# CH585M-R1.net
KiCad netlist of a schematic drawn in Altium Designer
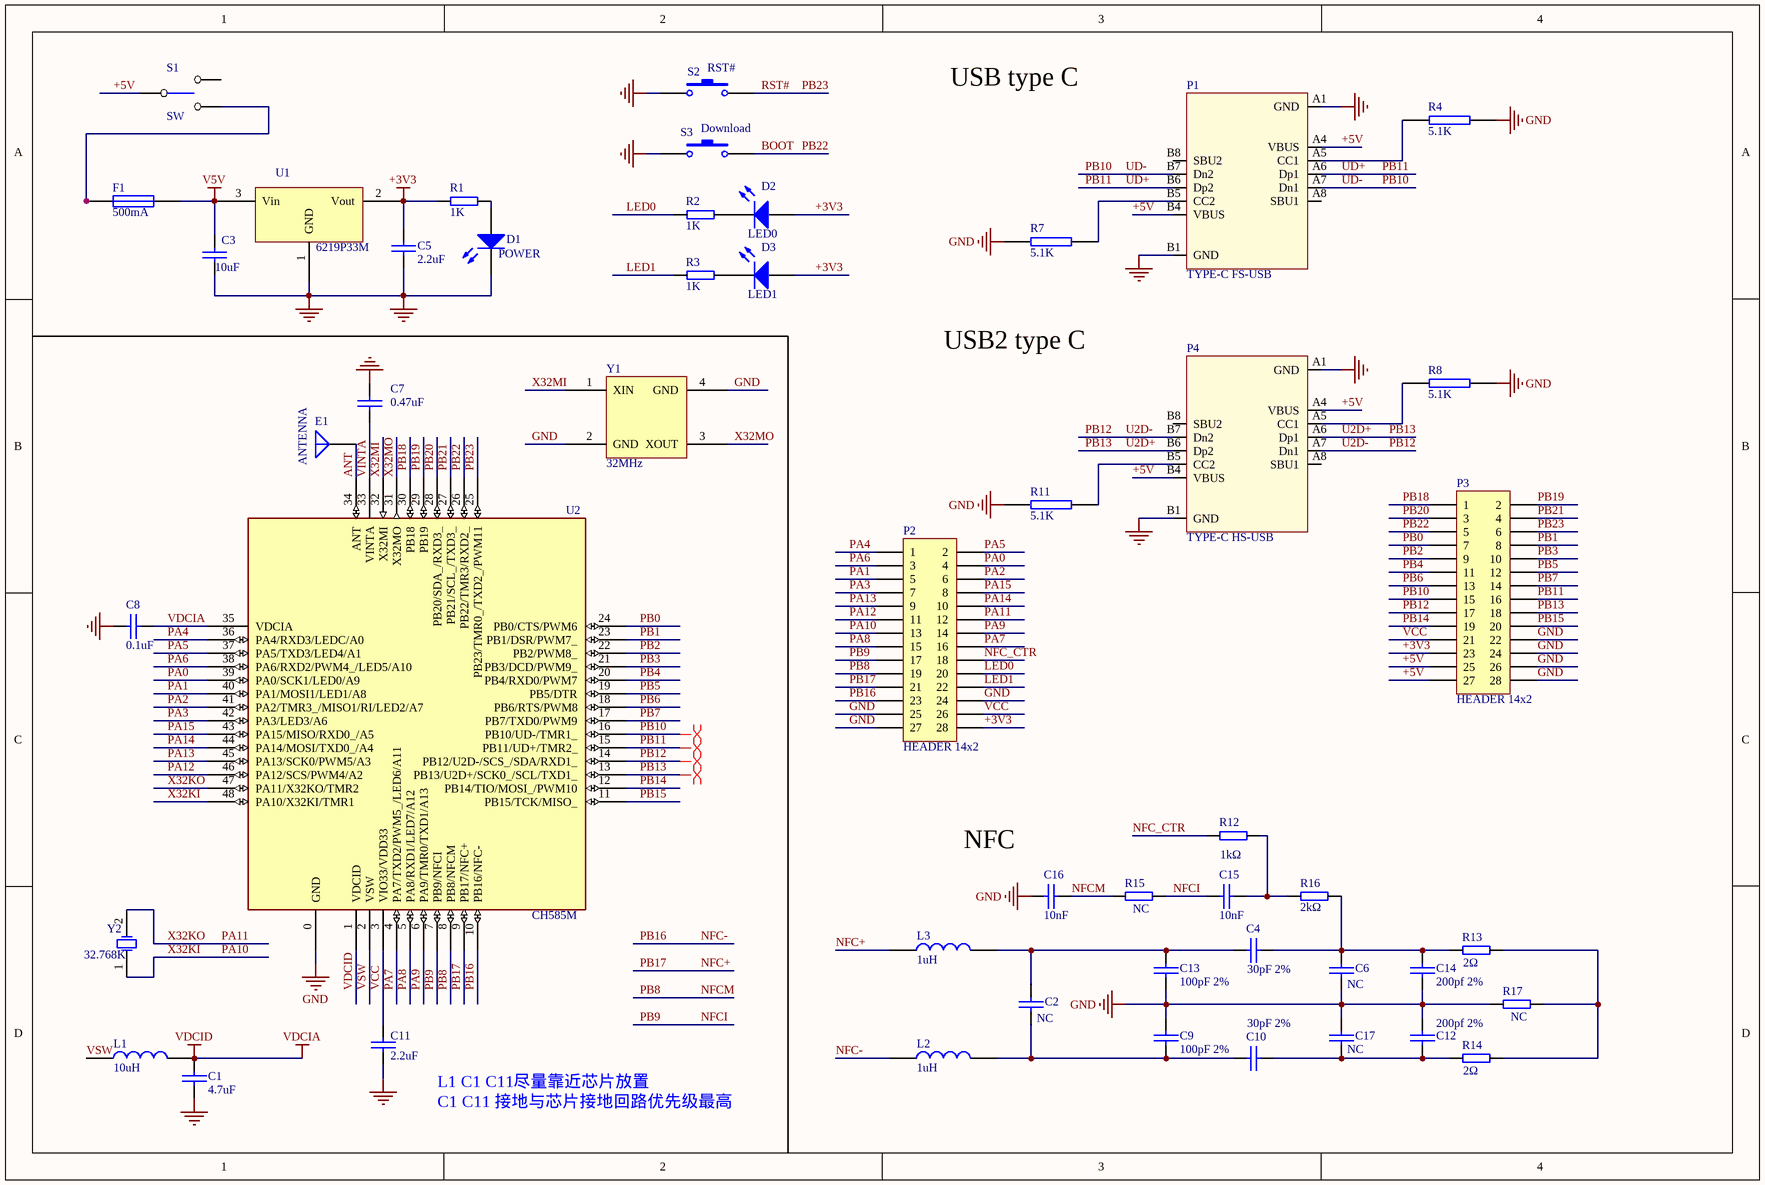
[diagram p0: CH585M-R1.SchDoc]

(export (version "E")
  (design (tool "Eeschema 10.0.6"))
  (components
    (comp (ref "C1")
      (value "4.7uF")
      (footprint "0402_C")
      (description "Capacitor")
      (libsource (lib "*") (part "CAP"))
    )
    (comp (ref "C2")
      (value "NC")
      (footprint "0402_C")
      (description "Capacitor")
      (libsource (lib "wch_sch_others") (part "CAP"))
    )
    (comp (ref "C3")
      (value "10uF")
      (footprint "0603_C")
      (description "Capacitor")
      (libsource (lib "") (part "CAP_1"))
    )
    (comp (ref "C4")
      (value "30pF 2%")
      (footprint "0402_C")
      (description "Capacitor")
      (libsource (lib "wch_sch_others") (part "CAP"))
    )
    (comp (ref "C5")
      (value "2.2uF")
      (footprint "0402_C")
      (description "Capacitor")
      (libsource (lib "") (part "CAP_1"))
    )
    (comp (ref "C6")
      (value "NC")
      (footprint "0402_C")
      (description "Capacitor")
      (libsource (lib "wch_sch_others") (part "CAP"))
    )
    (comp (ref "C7")
      (value "0.47uF")
      (footprint "0402_C")
      (description "Capacitor")
      (libsource (lib "") (part "CAP_1"))
    )
    (comp (ref "C8")
      (value "0.1uF")
      (footprint "0402_C")
      (description "Capacitor")
      (libsource (lib "") (part "CAP_1"))
    )
    (comp (ref "C9")
      (value "100pF 2%")
      (footprint "0402_C")
      (description "Capacitor")
      (libsource (lib "wch_sch_others") (part "CAP"))
    )
    (comp (ref "C10")
      (value "30pF 2%")
      (footprint "0402_C")
      (description "Capacitor")
      (libsource (lib "wch_sch_others") (part "CAP"))
    )
    (comp (ref "C11")
      (value "2.2uF")
      (footprint "0402_C")
      (description "Capacitor")
      (libsource (lib "") (part "CAP_1"))
    )
    (comp (ref "C12")
      (value "200pf 2%")
      (footprint "0402_C")
      (description "Capacitor")
      (libsource (lib "wch_sch_others") (part "CAP"))
    )
    (comp (ref "C13")
      (value "100pF 2%")
      (footprint "0402_C")
      (description "Capacitor")
      (libsource (lib "wch_sch_others") (part "CAP"))
    )
    (comp (ref "C14")
      (value "200pf 2%")
      (footprint "0402_C")
      (description "Capacitor")
      (libsource (lib "wch_sch_others") (part "CAP"))
    )
    (comp (ref "C15")
      (value "10nF")
      (footprint "0402_C")
      (description "Capacitor")
      (libsource (lib "wch_sch_others") (part "CAP"))
    )
    (comp (ref "C16")
      (value "10nF")
      (footprint "0402_C")
      (description "Capacitor")
      (libsource (lib "wch_sch_others") (part "CAP"))
    )
    (comp (ref "C17")
      (value "NC")
      (footprint "0402_C")
      (description "Capacitor")
      (libsource (lib "wch_sch_others") (part "CAP"))
    )
    (comp (ref "D1")
      (value "POWER")
      (footprint "0603+")
      (description "Typical INFRARED GaAs LED")
      (fields (field (name "PUBLISHER") "Altium Limited"))
      (libsource (lib "") (part "LED0_1"))
    )
    (comp (ref "D2")
      (value "LED0")
      (footprint "0603+")
      (description "Typical INFRARED GaAs LED")
      (fields (field (name "PUBLISHER") "Altium Limited"))
      (libsource (lib "Miscellaneous Devices") (part "LED0"))
    )
    (comp (ref "D3")
      (value "LED1")
      (footprint "0603+")
      (description "Typical INFRARED GaAs LED")
      (fields (field (name "PUBLISHER") "Altium Limited"))
      (libsource (lib "Miscellaneous Devices") (part "LED0"))
    )
    (comp (ref "E1")
      (value "ANTENNA")
      (footprint "ANT-F-1-2.4G-1.6mmFR4")
      (description "Generic Antenna")
      (libsource (lib "*") (part "ANTENNA"))
    )
    (comp (ref "F1")
      (value "500mA")
      (footprint "0603")
      (description "Fuse")
      (libsource (lib "*") (part "FUSE1"))
    )
    (comp (ref "L1") (value "10uH") (footprint "SMD_2x2mm") (libsource (lib "*") (part "INDUCTOR")))
    (comp (ref "L2") (value "1uH") (footprint "0603") (libsource (lib "*") (part "INDUCTOR")))
    (comp (ref "L3") (value "1uH") (footprint "0603") (libsource (lib "*") (part "INDUCTOR")))
    (comp (ref "P1")
      (value "TYPE-C FS-USB")
      (footprint "TYPE-C-Receptacle-2.0")
      (description "Type-C USB2.0 母座")
      (libsource (lib "Miscellaneous SCH Lib") (part "TYPE-C-Receptacle-2.0"))
    )
    (comp (ref "P2")
      (value "HEADER 14x2")
      (footprint "MYPCB:IDC28-2.54MM")
      (description "Header, 14-Pin, Dual row")
      (libsource (lib "wch_sch_others") (part "HEADER 14x2"))
    )
    (comp (ref "P3")
      (value "HEADER 14x2")
      (footprint "MYPCB:IDC28-2.54MM")
      (description "Header, 14-Pin, Dual row")
      (libsource (lib "wch_sch_others") (part "HEADER 14x2"))
    )
    (comp (ref "P4")
      (value "TYPE-C HS-USB")
      (footprint "TYPE-C-Receptacle-2.0")
      (description "Type-C USB2.0 母座")
      (libsource (lib "Miscellaneous SCH Lib") (part "TYPE-C-Receptacle-2.0"))
    )
    (comp (ref "R1") (value "1K") (footprint "0402") (libsource (lib "") (part "RES_1")))
    (comp (ref "R2") (value "1K") (footprint "0402") (libsource (lib "") (part "RES_1")))
    (comp (ref "R3") (value "1K") (footprint "0402") (libsource (lib "") (part "RES_1")))
    (comp (ref "R4") (value "5.1K") (footprint "0402") (libsource (lib "*") (part "RES2")))
    (comp (ref "R7") (value "5.1K") (footprint "0402") (libsource (lib "*") (part "RES2")))
    (comp (ref "R8") (value "5.1K") (footprint "0402") (libsource (lib "*") (part "RES2")))
    (comp (ref "R11") (value "5.1K") (footprint "0402") (libsource (lib "*") (part "RES2")))
    (comp (ref "R12") (value "1kΩ") (footprint "0402") (libsource (lib "wch_sch_others") (part "RES")))
    (comp (ref "R13") (value "2Ω") (footprint "0402") (libsource (lib "wch_sch_others") (part "RES")))
    (comp (ref "R14") (value "2Ω") (footprint "0402") (libsource (lib "wch_sch_others") (part "RES")))
    (comp (ref "R15") (value "NC") (footprint "0402") (libsource (lib "wch_sch_others") (part "RES")))
    (comp (ref "R16") (value "2kΩ") (footprint "0402") (libsource (lib "wch_sch_others") (part "RES")))
    (comp (ref "R17") (value "NC") (footprint "0402") (libsource (lib "wch_sch_others") (part "RES")))
    (comp (ref "S1") (value "SW") (footprint "SW1") (libsource (lib "MYSCH") (part "SW")))
    (comp (ref "S2")
      (value "RST#")
      (footprint "SMD_6.1x3.65x2.5mm-KEY")
      (description "Switch")
      (fields (field (name "PUBLISHER") "Altium Limited"))
      (libsource (lib "*") (part "SW-PB"))
    )
    (comp (ref "S3")
      (value "Download")
      (footprint "SMD_6.1x3.65x2.5mm-KEY")
      (description "Switch")
      (fields (field (name "PUBLISHER") "Altium Limited"))
      (libsource (lib "*") (part "SW-PB"))
    )
    (comp (ref "U1")
      (value "6219P33M")
      (footprint "SOT-23")
      (libsource (lib "wch_sch_others") (part "6219P33M"))
    )
    (comp (ref "U2")
      (value "CH585M")
      (footprint "QFN48_5X5")
      (description "RISC-V MCU with BLE/HSUSB/USB/NFC/ADC/PWM/2*SPI/I2C/4*UART/LCD")
      (libsource (lib "CHXXX") (part "CH585M"))
    )
    (comp (ref "Y1") (value "32MHz") (footprint "XT3225") (libsource (lib "wch_sch_others") (part "晶体")))
    (comp (ref "Y2")
      (value "32.768K")
      (footprint "fc-135")
      (description "Crystal Oscillator")
      (fields (field (name "PUBLISHER") "Altium Limited"))
      (libsource (lib "*") (part "XTAL"))
    )
  )
  (nets
    (net (code "1") (name "+3V3") (class "Default")
      (node (ref "C5") (pin "1") (pinfunction "1_1") (pintype "passive"))
      (node (ref "D2") (pin "1") (pinfunction "A_1") (pintype "passive"))
      (node (ref "D3") (pin "1") (pinfunction "A_1") (pintype "passive"))
      (node (ref "P2") (pin "28") (pinfunction "28_28") (pintype "passive"))
      (node (ref "P3") (pin "23") (pinfunction "23_23") (pintype "passive"))
      (node (ref "R1") (pin "2") (pintype "passive"))
      (node (ref "U1") (pin "2") (pinfunction "Vout_2") (pintype "passive"))
    )
    (net (code "2") (name "/+5V") (class "Default")
      (node (ref "P1") (pin "A4") (pinfunction "VBUS_A4") (pintype "passive"))
      (node (ref "P1") (pin "B4") (pinfunction "VBUS_B4") (pintype "passive"))
      (node (ref "P3") (pin "25") (pinfunction "25_25") (pintype "passive"))
      (node (ref "P3") (pin "27") (pinfunction "27_27") (pintype "passive"))
      (node (ref "P4") (pin "A4") (pinfunction "VBUS_A4") (pintype "passive"))
      (node (ref "P4") (pin "B4") (pinfunction "VBUS_B4") (pintype "passive"))
      (node (ref "S1") (pin "1") (pinfunction "1_1") (pintype "passive"))
    )
    (net (code "3") (name "/ANT") (class "Default")
      (node (ref "E1") (pin "1") (pinfunction "A_1") (pintype "passive"))
      (node (ref "U2") (pin "34") (pinfunction "ANT_34") (pintype "bidirectional"))
    )
    (net (code "4") (name "/BOOT") (class "Default")
      (node (ref "P3") (pin "5") (pinfunction "5_5") (pintype "passive"))
      (node (ref "S3") (pin "2") (pinfunction "2_2") (pintype "passive"))
      (node (ref "U2") (pin "26") (pinfunction "PB22/TMR3/RXD2__26") (pintype "bidirectional"))
    )
    (net (code "5") (name "/LED0") (class "Default")
      (node (ref "P2") (pin "20") (pinfunction "20_20") (pintype "passive"))
      (node (ref "R2") (pin "1") (pintype "passive"))
    )
    (net (code "6") (name "/LED1") (class "Default")
      (node (ref "P2") (pin "22") (pinfunction "22_22") (pintype "passive"))
      (node (ref "R3") (pin "1") (pintype "passive"))
    )
    (net (code "7") (name "/NFC+") (class "Default")
      (node (ref "L3") (pin "1") (pinfunction "1_1") (pintype "passive"))
      (node (ref "P2") (pin "21") (pinfunction "21_21") (pintype "passive"))
      (node (ref "U2") (pin "9") (pinfunction "PB17/NFC+_9") (pintype "bidirectional"))
    )
    (net (code "8") (name "/NFC-") (class "Default")
      (node (ref "L2") (pin "1") (pinfunction "1_1") (pintype "passive"))
      (node (ref "P2") (pin "23") (pinfunction "23_23") (pintype "passive"))
      (node (ref "U2") (pin "10") (pinfunction "PB16/NFC-_10") (pintype "bidirectional"))
    )
    (net (code "9") (name "/NFCI") (class "Default")
      (node (ref "C15") (pin "1") (pinfunction "1_1") (pintype "passive"))
      (node (ref "P2") (pin "17") (pinfunction "17_17") (pintype "passive"))
      (node (ref "R15") (pin "1") (pintype "passive"))
      (node (ref "U2") (pin "7") (pinfunction "PB9/NFCI_7") (pintype "bidirectional"))
    )
    (net (code "10") (name "/NFCM") (class "Default")
      (node (ref "C16") (pin "1") (pinfunction "1_1") (pintype "passive"))
      (node (ref "P2") (pin "19") (pinfunction "19_19") (pintype "passive"))
      (node (ref "R15") (pin "2") (pintype "passive"))
      (node (ref "U2") (pin "8") (pinfunction "PB8/NFCM_8") (pintype "bidirectional"))
    )
    (net (code "11") (name "/NFC_CTR") (class "Default")
      (node (ref "P2") (pin "18") (pinfunction "18_18") (pintype "passive"))
      (node (ref "R12") (pin "2") (pintype "passive"))
    )
    (net (code "12") (name "/PA0") (class "Default")
      (node (ref "P2") (pin "4") (pinfunction "4_4") (pintype "passive"))
      (node (ref "U2") (pin "39") (pinfunction "PA0/SCK1/LED0/A9_39") (pintype "bidirectional"))
    )
    (net (code "13") (name "/PA1") (class "Default")
      (node (ref "P2") (pin "5") (pinfunction "5_5") (pintype "passive"))
      (node (ref "U2") (pin "40") (pinfunction "PA1/MOSI1/LED1/A8_40") (pintype "bidirectional"))
    )
    (net (code "14") (name "/PA2") (class "Default")
      (node (ref "P2") (pin "6") (pinfunction "6_6") (pintype "passive"))
      (node (ref "U2") (pin "41") (pinfunction "PA2/TMR3_/MISO1/RI/LED2/A7_41") (pintype "bidirectional"))
    )
    (net (code "15") (name "/PA3") (class "Default")
      (node (ref "P2") (pin "7") (pinfunction "7_7") (pintype "passive"))
      (node (ref "U2") (pin "42") (pinfunction "PA3/LED3/A6_42") (pintype "bidirectional"))
    )
    (net (code "16") (name "/PA4") (class "Default")
      (node (ref "P2") (pin "1") (pinfunction "1_1") (pintype "passive"))
      (node (ref "U2") (pin "36") (pinfunction "PA4/RXD3/LEDC/A0_36") (pintype "bidirectional"))
    )
    (net (code "17") (name "/PA5") (class "Default")
      (node (ref "P2") (pin "2") (pinfunction "2_2") (pintype "passive"))
      (node (ref "U2") (pin "37") (pinfunction "PA5/TXD3/LED4/A1_37") (pintype "bidirectional"))
    )
    (net (code "18") (name "/PA6") (class "Default")
      (node (ref "P2") (pin "3") (pinfunction "3_3") (pintype "passive"))
      (node (ref "U2") (pin "38") (pinfunction "PA6/RXD2/PWM4_/LED5/A10_38") (pintype "bidirectional"))
    )
    (net (code "19") (name "/PA7") (class "Default")
      (node (ref "P2") (pin "16") (pinfunction "16_16") (pintype "passive"))
      (node (ref "U2") (pin "4") (pinfunction "PA7/TXD2/PWM5_/LED6/A11_4") (pintype "bidirectional"))
    )
    (net (code "20") (name "/PA8") (class "Default")
      (node (ref "P2") (pin "15") (pinfunction "15_15") (pintype "passive"))
      (node (ref "U2") (pin "5") (pinfunction "PA8/RXD1/LED7/A12_5") (pintype "bidirectional"))
    )
    (net (code "21") (name "/PA9") (class "Default")
      (node (ref "P2") (pin "14") (pinfunction "14_14") (pintype "passive"))
      (node (ref "U2") (pin "6") (pinfunction "PA9/TMR0/TXD1/A13_6") (pintype "bidirectional"))
    )
    (net (code "22") (name "/PA10") (class "Default")
      (node (ref "P2") (pin "13") (pinfunction "13_13") (pintype "passive"))
      (node (ref "U2") (pin "48") (pinfunction "PA10/X32KI/TMR1_48") (pintype "bidirectional"))
      (node (ref "Y2") (pin "1") (pinfunction "OSC1_1") (pintype "passive"))
    )
    (net (code "23") (name "/PA11") (class "Default")
      (node (ref "P2") (pin "12") (pinfunction "12_12") (pintype "passive"))
      (node (ref "U2") (pin "47") (pinfunction "PA11/X32KO/TMR2_47") (pintype "bidirectional"))
      (node (ref "Y2") (pin "2") (pinfunction "OSC2_2") (pintype "passive"))
    )
    (net (code "24") (name "/PA12") (class "Default")
      (node (ref "P2") (pin "11") (pinfunction "11_11") (pintype "passive"))
      (node (ref "U2") (pin "46") (pinfunction "PA12/SCS/PWM4/A2_46") (pintype "bidirectional"))
    )
    (net (code "25") (name "/PA13") (class "Default")
      (node (ref "P2") (pin "9") (pinfunction "9_9") (pintype "passive"))
      (node (ref "U2") (pin "45") (pinfunction "PA13/SCK0/PWM5/A3_45") (pintype "bidirectional"))
    )
    (net (code "26") (name "/PA14") (class "Default")
      (node (ref "P2") (pin "10") (pinfunction "10_10") (pintype "passive"))
      (node (ref "U2") (pin "44") (pinfunction "PA14/MOSI/TXD0_/A4_44") (pintype "bidirectional"))
    )
    (net (code "27") (name "/PA15") (class "Default")
      (node (ref "P2") (pin "8") (pinfunction "8_8") (pintype "passive"))
      (node (ref "U2") (pin "43") (pinfunction "PA15/MISO/RXD0_/A5_43") (pintype "bidirectional"))
    )
    (net (code "28") (name "/PB0") (class "Default")
      (node (ref "P3") (pin "7") (pinfunction "7_7") (pintype "passive"))
      (node (ref "U2") (pin "24") (pinfunction "PB0/CTS/PWM6_24") (pintype "bidirectional"))
    )
    (net (code "29") (name "/PB1") (class "Default")
      (node (ref "P3") (pin "8") (pinfunction "8_8") (pintype "passive"))
      (node (ref "U2") (pin "23") (pinfunction "PB1/DSR/PWM7__23") (pintype "bidirectional"))
    )
    (net (code "30") (name "/PB2") (class "Default")
      (node (ref "P3") (pin "9") (pinfunction "9_9") (pintype "passive"))
      (node (ref "U2") (pin "22") (pinfunction "PB2/PWM8__22") (pintype "bidirectional"))
    )
    (net (code "31") (name "/PB3") (class "Default")
      (node (ref "P3") (pin "10") (pinfunction "10_10") (pintype "passive"))
      (node (ref "U2") (pin "21") (pinfunction "PB3/DCD/PWM9__21") (pintype "bidirectional"))
    )
    (net (code "32") (name "/PB4") (class "Default")
      (node (ref "P3") (pin "11") (pinfunction "11_11") (pintype "passive"))
      (node (ref "U2") (pin "20") (pinfunction "PB4/RXD0/PWM7_20") (pintype "bidirectional"))
    )
    (net (code "33") (name "/PB5") (class "Default")
      (node (ref "P3") (pin "12") (pinfunction "12_12") (pintype "passive"))
      (node (ref "U2") (pin "19") (pinfunction "PB5/DTR_19") (pintype "bidirectional"))
    )
    (net (code "34") (name "/PB6") (class "Default")
      (node (ref "P3") (pin "13") (pinfunction "13_13") (pintype "passive"))
      (node (ref "U2") (pin "18") (pinfunction "PB6/RTS/PWM8_18") (pintype "bidirectional"))
    )
    (net (code "35") (name "/PB7") (class "Default")
      (node (ref "P3") (pin "14") (pinfunction "14_14") (pintype "passive"))
      (node (ref "U2") (pin "17") (pinfunction "PB7/TXD0/PWM9_17") (pintype "bidirectional"))
    )
    (net (code "36") (name "/PB10") (class "Default")
      (node (ref "P1") (pin "A7") (pinfunction "Dn1_A7") (pintype "passive"))
      (node (ref "P1") (pin "B7") (pinfunction "Dn2_B7") (pintype "passive"))
      (node (ref "P3") (pin "15") (pinfunction "15_15") (pintype "passive"))
      (node (ref "U2") (pin "16") (pinfunction "PB10/UD-/TMR1__16") (pintype "bidirectional"))
    )
    (net (code "37") (name "/PB11") (class "Default")
      (node (ref "P1") (pin "A6") (pinfunction "Dp1_A6") (pintype "passive"))
      (node (ref "P1") (pin "B6") (pinfunction "Dp2_B6") (pintype "passive"))
      (node (ref "P3") (pin "16") (pinfunction "16_16") (pintype "passive"))
      (node (ref "U2") (pin "15") (pinfunction "PB11/UD+/TMR2__15") (pintype "bidirectional"))
    )
    (net (code "38") (name "/PB12") (class "Default")
      (node (ref "P3") (pin "17") (pinfunction "17_17") (pintype "passive"))
      (node (ref "P4") (pin "A7") (pinfunction "Dn1_A7") (pintype "passive"))
      (node (ref "P4") (pin "B7") (pinfunction "Dn2_B7") (pintype "passive"))
      (node (ref "U2") (pin "14") (pinfunction "PB12/U2D-/SCS_/SDA/RXD1__14") (pintype "bidirectional"))
    )
    (net (code "39") (name "/PB13") (class "Default")
      (node (ref "P3") (pin "18") (pinfunction "18_18") (pintype "passive"))
      (node (ref "P4") (pin "A6") (pinfunction "Dp1_A6") (pintype "passive"))
      (node (ref "P4") (pin "B6") (pinfunction "Dp2_B6") (pintype "passive"))
      (node (ref "U2") (pin "13") (pinfunction "PB13/U2D+/SCK0_/SCL/TXD1__13") (pintype "bidirectional"))
    )
    (net (code "40") (name "/PB14") (class "Default")
      (node (ref "P3") (pin "19") (pinfunction "19_19") (pintype "passive"))
      (node (ref "U2") (pin "12") (pinfunction "PB14/TIO/MOSI_/PWM10_12") (pintype "bidirectional"))
    )
    (net (code "41") (name "/PB15") (class "Default")
      (node (ref "P3") (pin "20") (pinfunction "20_20") (pintype "passive"))
      (node (ref "U2") (pin "11") (pinfunction "PB15/TCK/MISO__11") (pintype "bidirectional"))
    )
    (net (code "42") (name "/PB18") (class "Default")
      (node (ref "P3") (pin "1") (pinfunction "1_1") (pintype "passive"))
      (node (ref "U2") (pin "30") (pinfunction "PB18_30") (pintype "bidirectional"))
    )
    (net (code "43") (name "/PB19") (class "Default")
      (node (ref "P3") (pin "2") (pinfunction "2_2") (pintype "passive"))
      (node (ref "U2") (pin "29") (pinfunction "PB19_29") (pintype "bidirectional"))
    )
    (net (code "44") (name "/PB20") (class "Default")
      (node (ref "P3") (pin "3") (pinfunction "3_3") (pintype "passive"))
      (node (ref "U2") (pin "28") (pinfunction "PB20/SDA_/RXD3__28") (pintype "bidirectional"))
    )
    (net (code "45") (name "/PB21") (class "Default")
      (node (ref "P3") (pin "4") (pinfunction "4_4") (pintype "passive"))
      (node (ref "U2") (pin "27") (pinfunction "PB21/SCL_/TXD3__27") (pintype "bidirectional"))
    )
    (net (code "46") (name "/PB23") (class "Default")
      (node (ref "P3") (pin "6") (pinfunction "6_6") (pintype "passive"))
      (node (ref "S2") (pin "2") (pinfunction "2_2") (pintype "passive"))
      (node (ref "U2") (pin "25") (pinfunction "PB23/TMR0_/TXD2_/PWM11_25") (pintype "bidirectional"))
    )
    (net (code "47") (name "/VCC") (class "Default")
      (node (ref "C11") (pin "2") (pinfunction "2_2") (pintype "passive"))
      (node (ref "P2") (pin "26") (pinfunction "26_26") (pintype "passive"))
      (node (ref "P3") (pin "21") (pinfunction "21_21") (pintype "passive"))
      (node (ref "U2") (pin "3") (pinfunction "VIO33/VDD33_3") (pintype "power_in"))
    )
    (net (code "48") (name "/VINTA") (class "Default")
      (node (ref "C7") (pin "1") (pinfunction "1_1") (pintype "passive"))
      (node (ref "U2") (pin "33") (pinfunction "VINTA_33") (pintype "power_in"))
    )
    (net (code "49") (name "/VSW") (class "Default")
      (node (ref "L1") (pin "1") (pinfunction "1_1") (pintype "passive"))
      (node (ref "U2") (pin "2") (pinfunction "VSW_2") (pintype "power_in"))
    )
    (net (code "50") (name "/X32MI") (class "Default")
      (node (ref "U2") (pin "32") (pinfunction "X32MI_32") (pintype "input"))
      (node (ref "Y1") (pin "1") (pinfunction "XIN_1") (pintype "passive"))
    )
    (net (code "51") (name "/X32MO") (class "Default")
      (node (ref "U2") (pin "31") (pinfunction "X32MO_31") (pintype "output"))
      (node (ref "Y1") (pin "3") (pinfunction "XOUT_3") (pintype "passive"))
    )
    (net (code "52") (name "GND") (class "Default")
      (node (ref "C1") (pin "1") (pinfunction "1_1") (pintype "passive"))
      (node (ref "C11") (pin "1") (pinfunction "1_1") (pintype "passive"))
      (node (ref "C12") (pin "2") (pinfunction "2_2") (pintype "passive"))
      (node (ref "C13") (pin "1") (pinfunction "1_1") (pintype "passive"))
      (node (ref "C14") (pin "1") (pinfunction "1_1") (pintype "passive"))
      (node (ref "C16") (pin "2") (pinfunction "2_2") (pintype "passive"))
      (node (ref "C17") (pin "2") (pinfunction "2_2") (pintype "passive"))
      (node (ref "C3") (pin "2") (pinfunction "2_2") (pintype "passive"))
      (node (ref "C5") (pin "2") (pinfunction "2_2") (pintype "passive"))
      (node (ref "C6") (pin "1") (pinfunction "1_1") (pintype "passive"))
      (node (ref "C7") (pin "2") (pinfunction "2_2") (pintype "passive"))
      (node (ref "C8") (pin "2") (pinfunction "2_2") (pintype "passive"))
      (node (ref "C9") (pin "2") (pinfunction "2_2") (pintype "passive"))
      (node (ref "D1") (pin "2") (pinfunction "K_2") (pintype "passive"))
      (node (ref "P1") (pin "A1") (pinfunction "GND_A1") (pintype "passive"))
      (node (ref "P1") (pin "B1") (pinfunction "GND_B1") (pintype "passive"))
      (node (ref "P2") (pin "24") (pinfunction "24_24") (pintype "passive"))
      (node (ref "P2") (pin "25") (pinfunction "25_25") (pintype "passive"))
      (node (ref "P2") (pin "27") (pinfunction "27_27") (pintype "passive"))
      (node (ref "P3") (pin "22") (pinfunction "22_22") (pintype "passive"))
      (node (ref "P3") (pin "24") (pinfunction "24_24") (pintype "passive"))
      (node (ref "P3") (pin "26") (pinfunction "26_26") (pintype "passive"))
      (node (ref "P3") (pin "28") (pinfunction "28_28") (pintype "passive"))
      (node (ref "P4") (pin "A1") (pinfunction "GND_A1") (pintype "passive"))
      (node (ref "P4") (pin "B1") (pinfunction "GND_B1") (pintype "passive"))
      (node (ref "R11") (pin "2") (pinfunction "2_2") (pintype "passive"))
      (node (ref "R17") (pin "2") (pintype "passive"))
      (node (ref "R4") (pin "1") (pinfunction "1_1") (pintype "passive"))
      (node (ref "R7") (pin "2") (pinfunction "2_2") (pintype "passive"))
      (node (ref "R8") (pin "1") (pinfunction "1_1") (pintype "passive"))
      (node (ref "S2") (pin "1") (pinfunction "1_1") (pintype "passive"))
      (node (ref "S3") (pin "1") (pinfunction "1_1") (pintype "passive"))
      (node (ref "U1") (pin "1") (pinfunction "GND_1") (pintype "passive"))
      (node (ref "U2") (pin "0") (pinfunction "GND_0") (pintype "power_in"))
      (node (ref "Y1") (pin "2") (pinfunction "GND_2") (pintype "passive"))
      (node (ref "Y1") (pin "4") (pinfunction "GND_4") (pintype "passive"))
    )
    (net (code "53") (name "Net-(C10-Pad1)") (class "Default")
      (node (ref "C10") (pin "1") (pinfunction "1_1") (pintype "passive"))
      (node (ref "C2") (pin "1") (pinfunction "1_1") (pintype "passive"))
      (node (ref "C9") (pin "1") (pinfunction "1_1") (pintype "passive"))
      (node (ref "L2") (pin "2") (pinfunction "2_2") (pintype "passive"))
    )
    (net (code "54") (name "Net-(C10-Pad2)") (class "Default")
      (node (ref "C10") (pin "2") (pinfunction "2_2") (pintype "passive"))
      (node (ref "C12") (pin "1") (pinfunction "1_1") (pintype "passive"))
      (node (ref "C17") (pin "1") (pinfunction "1_1") (pintype "passive"))
      (node (ref "R14") (pin "1") (pintype "passive"))
    )
    (net (code "55") (name "Net-(C13-Pad2)") (class "Default")
      (node (ref "C13") (pin "2") (pinfunction "2_2") (pintype "passive"))
      (node (ref "C2") (pin "2") (pinfunction "2_2") (pintype "passive"))
      (node (ref "C4") (pin "1") (pinfunction "1_1") (pintype "passive"))
      (node (ref "L3") (pin "2") (pinfunction "2_2") (pintype "passive"))
    )
    (net (code "56") (name "Net-(C14-Pad2)") (class "Default")
      (node (ref "C14") (pin "2") (pinfunction "2_2") (pintype "passive"))
      (node (ref "C4") (pin "2") (pinfunction "2_2") (pintype "passive"))
      (node (ref "C6") (pin "2") (pinfunction "2_2") (pintype "passive"))
      (node (ref "R13") (pin "1") (pintype "passive"))
      (node (ref "R16") (pin "1") (pintype "passive"))
    )
    (net (code "57") (name "Net-(C15-Pad2)") (class "Default")
      (node (ref "C15") (pin "2") (pinfunction "2_2") (pintype "passive"))
      (node (ref "R12") (pin "1") (pintype "passive"))
      (node (ref "R16") (pin "2") (pintype "passive"))
    )
    (net (code "58") (name "Net-(D1-A)") (class "Default")
      (node (ref "D1") (pin "1") (pinfunction "A_1") (pintype "passive"))
      (node (ref "R1") (pin "1") (pintype "passive"))
    )
    (net (code "59") (name "Net-(D2-K)") (class "Default")
      (node (ref "D2") (pin "2") (pinfunction "K_2") (pintype "passive"))
      (node (ref "R2") (pin "2") (pintype "passive"))
    )
    (net (code "60") (name "Net-(D3-K)") (class "Default")
      (node (ref "D3") (pin "2") (pinfunction "K_2") (pintype "passive"))
      (node (ref "R3") (pin "2") (pintype "passive"))
    )
    (net (code "61") (name "Net-(F1-Pad1)") (class "Default")
      (node (ref "F1") (pin "1") (pinfunction "1_1") (pintype "passive"))
      (node (ref "S1") (pin "2") (pinfunction "2_2") (pintype "passive"))
    )
    (net (code "62") (name "Net-(P1-CC1)") (class "Default")
      (node (ref "P1") (pin "A5") (pinfunction "CC1_A5") (pintype "passive"))
      (node (ref "R4") (pin "2") (pinfunction "2_2") (pintype "passive"))
    )
    (net (code "63") (name "Net-(P1-CC2)") (class "Default")
      (node (ref "P1") (pin "B5") (pinfunction "CC2_B5") (pintype "passive"))
      (node (ref "R7") (pin "1") (pinfunction "1_1") (pintype "passive"))
    )
    (net (code "64") (name "Net-(P4-CC1)") (class "Default")
      (node (ref "P4") (pin "A5") (pinfunction "CC1_A5") (pintype "passive"))
      (node (ref "R8") (pin "2") (pinfunction "2_2") (pintype "passive"))
    )
    (net (code "65") (name "Net-(P4-CC2)") (class "Default")
      (node (ref "P4") (pin "B5") (pinfunction "CC2_B5") (pintype "passive"))
      (node (ref "R11") (pin "1") (pinfunction "1_1") (pintype "passive"))
    )
    (net (code "66") (name "Net-(R13-Pad2)") (class "Default")
      (node (ref "R13") (pin "2") (pintype "passive"))
      (node (ref "R14") (pin "2") (pintype "passive"))
      (node (ref "R17") (pin "1") (pintype "passive"))
    )
    (net (code "67") (name "V5V") (class "Default")
      (node (ref "C3") (pin "1") (pinfunction "1_1") (pintype "passive"))
      (node (ref "F1") (pin "2") (pinfunction "2_2") (pintype "passive"))
      (node (ref "U1") (pin "3") (pinfunction "Vin_3") (pintype "passive"))
    )
    (net (code "68") (name "VDCIA") (class "Default")
      (node (ref "C1") (pin "2") (pinfunction "2_2") (pintype "passive"))
      (node (ref "C8") (pin "1") (pinfunction "1_1") (pintype "passive"))
      (node (ref "L1") (pin "2") (pinfunction "2_2") (pintype "passive"))
      (node (ref "U2") (pin "1") (pinfunction "VDCID_1") (pintype "power_in"))
      (node (ref "U2") (pin "35") (pinfunction "VDCIA_35") (pintype "power_in"))
    )
    (net (code "69") (name "unconnected-(P1-SBU1-PadA8)") (class "Default")
      (node (ref "P1") (pin "A8") (pinfunction "SBU1_A8") (pintype "passive"))
    )
    (net (code "70") (name "unconnected-(P1-SBU2-PadB8)") (class "Default")
      (node (ref "P1") (pin "B8") (pinfunction "SBU2_B8") (pintype "passive"))
    )
    (net (code "71") (name "unconnected-(P4-SBU1-PadA8)") (class "Default")
      (node (ref "P4") (pin "A8") (pinfunction "SBU1_A8") (pintype "passive"))
    )
    (net (code "72") (name "unconnected-(P4-SBU2-PadB8)") (class "Default")
      (node (ref "P4") (pin "B8") (pinfunction "SBU2_B8") (pintype "passive"))
    )
    (net (code "73") (name "unconnected-(S1-Pad3)") (class "Default")
      (node (ref "S1") (pin "3") (pinfunction "3_3") (pintype "passive"))
    )
  )
)
